# Step_motor_1.net
KiCad netlist of a schematic drawn in Altium Designer
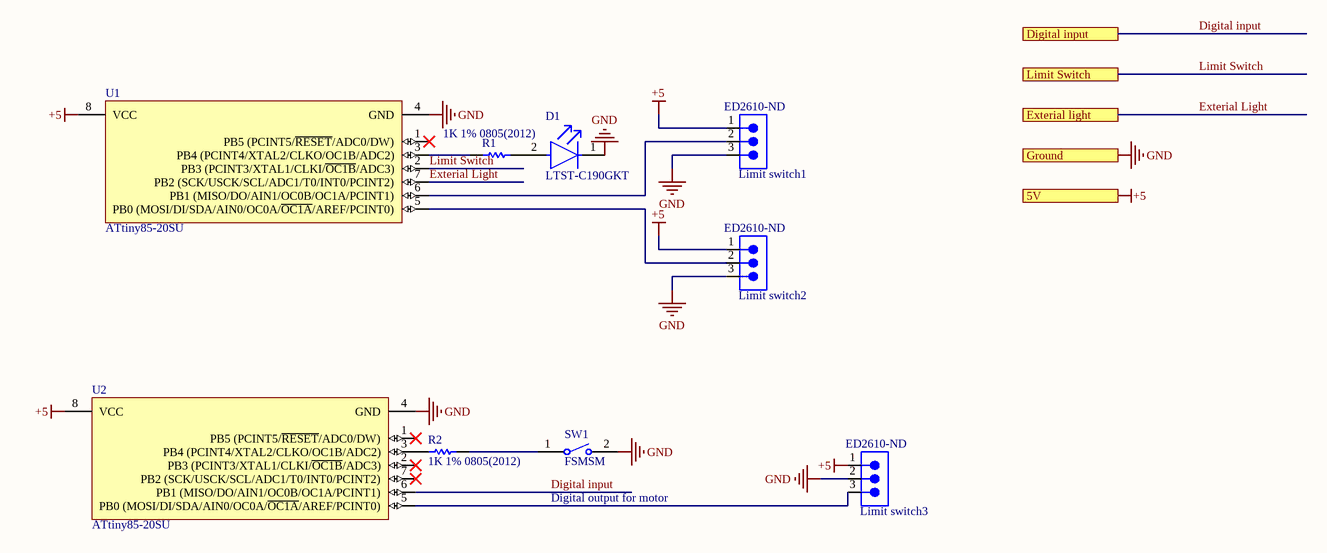
[diagram p0: Step motor 1.SchDoc]

(export (version "E")
  (design (tool "Eeschema 10.0.6"))
  (components
    (comp (ref "D1")
      (value "LTST-C190GKT")
      (footprint "FP-LTST-C190GKT-MFG")
      (description "LED GREEN CLEAR CHIP SMD")
      (fields (field (name "VOLTAGE") "2V"))
      (libsource (lib "Altium Content Vault") (part "8706943c75ba83719d021d2fdc84c58"))
    )
    (comp (ref "Limit switch1")
      (value "1x3 header 90120-0123")
      (footprint "1x3 - OSTTC032162")
      (description "HDR 1x3, 2.54mm Pitch, Vert TH")
      (fields
        (field (name "MANUFACTURER PART #") "90120-0123")
        (field (name "MANUFACTURER") "Molex")
        (field (name "SUPPLIER PART NUMBER 2") "ED2610-ND")
      )
      (libsource (lib "Connectors") (part "1x3 header 90120-0123"))
    )
    (comp (ref "Limit switch2")
      (value "1x3 header 90120-0123")
      (footprint "1x3 - OSTTC032162")
      (description "HDR 1x3, 2.54mm Pitch, Vert TH")
      (fields
        (field (name "MANUFACTURER PART #") "90120-0123")
        (field (name "MANUFACTURER") "Molex")
        (field (name "SUPPLIER PART NUMBER 2") "ED2610-ND")
      )
      (libsource (lib "Connectors") (part "1x3 header 90120-0123"))
    )
    (comp (ref "Limit switch3")
      (value "1x3 header 90120-0123")
      (footprint "1x3 - OSTTC032162")
      (description "HDR 1x3, 2.54mm Pitch, Vert TH")
      (fields
        (field (name "MANUFACTURER PART #") "90120-0123")
        (field (name "MANUFACTURER") "Molex")
        (field (name "SUPPLIER PART NUMBER 2") "ED2610-ND")
      )
      (libsource (lib "Connectors") (part "1x3 header 90120-0123"))
    )
    (comp (ref "R1")
      (value "1K 1% 0805(2012)")
      (footprint "RESC0805(2012)_M")
      (description "1K 0.125W 1% 0805 (2012 Metric)  SMD")
      (fields (field (name "TOLERANCE") "1 %") (field (name "POWER") "0.125 W"))
      (libsource (lib "Altium Content Vault") (part "RES"))
    )
    (comp (ref "R2")
      (value "1K 1% 0805(2012)")
      (footprint "RESC0805(2012)_M")
      (description "1K 0.125W 1% 0805 (2012 Metric)  SMD")
      (fields (field (name "TOLERANCE") "1 %") (field (name "POWER") "0.125 W"))
      (libsource (lib "Altium Content Vault") (part "RES"))
    )
    (comp (ref "SW1")
      (value "FSMSM")
      (footprint "TECO-FSMSM-2_V")
      (description "FSMSM Push Button Switch, 50 mA, -35 to 85 degC, 2-Pin SMD, RoHS, Bulk")
      (fields (field (name "MANUFACTURER") "TE Connectivity"))
      (libsource (lib "Altium Content Vault") (part "SW-SPST-2_C"))
    )
    (comp (ref "U1")
      (value "ATtiny85-20SU")
      (footprint "8S2_M")
      (libsource (lib "Altium Content Vault") (part "MC-8B-ATT25-IL8"))
    )
    (comp (ref "U2")
      (value "ATtiny85-20SU")
      (footprint "8S2_M")
      (libsource (lib "Altium Content Vault") (part "MC-8B-ATT25-IL8"))
    )
  )
  (nets
    (net (code "1") (name "+5") (class "Default")
      (node (ref "Limit switch1") (pin "1") (pinfunction "1_1") (pintype "passive"))
      (node (ref "Limit switch2") (pin "1") (pinfunction "1_1") (pintype "passive"))
      (node (ref "Limit switch3") (pin "1") (pinfunction "1_1") (pintype "passive"))
      (node (ref "U1") (pin "8") (pinfunction "VCC_8") (pintype "power_in"))
      (node (ref "U2") (pin "8") (pinfunction "VCC_8") (pintype "power_in"))
    )
    (net (code "2") (name "/Digital input") (class "Default")
      (node (ref "U2") (pin "6") (pinfunction "PB1_(MISO/DO/AIN1/OC0B/OC1A/PCINT1)_6") (pintype "bidirectional"))
    )
    (net (code "3") (name "/Exterial Light") (class "Default")
      (node (ref "U1") (pin "7") (pinfunction "PB2_(SCK/USCK/SCL/ADC1/T0/INT0/PCINT2)_7") (pintype "bidirectional"))
    )
    (net (code "4") (name "/Limit Switch") (class "Default")
      (node (ref "U1") (pin "2") (pinfunction "PB3_(PCINT3/XTAL1/CLKI/~{OC1B}/ADC3)_2") (pintype "bidirectional"))
    )
    (net (code "5") (name "GND") (class "Default")
      (node (ref "D1") (pin "1") (pinfunction "C_1") (pintype "passive"))
      (node (ref "Limit switch1") (pin "3") (pinfunction "3_3") (pintype "passive"))
      (node (ref "Limit switch2") (pin "3") (pinfunction "3_3") (pintype "passive"))
      (node (ref "Limit switch3") (pin "2") (pinfunction "2_2") (pintype "passive"))
      (node (ref "SW1") (pin "2") (pinfunction "2_2") (pintype "passive"))
      (node (ref "U1") (pin "4") (pinfunction "GND_4") (pintype "power_in"))
      (node (ref "U2") (pin "4") (pinfunction "GND_4") (pintype "power_in"))
    )
    (net (code "6") (name "Net-(D1-A)") (class "Default")
      (node (ref "D1") (pin "2") (pinfunction "A_2") (pintype "passive"))
      (node (ref "R1") (pin "2") (pinfunction "2_2") (pintype "passive"))
    )
    (net (code "7") (name "Net-(R2-Pad2)") (class "Default")
      (node (ref "R2") (pin "2") (pinfunction "2_2") (pintype "passive"))
      (node (ref "SW1") (pin "1") (pinfunction "1_1") (pintype "passive"))
    )
    (net (code "8") (name "Net-(U1-PB0_(MOSI{slash}DI{slash}SDA{slash}AIN0{slash}OC0A{slash}~{OC1A}{slash}AREF{slash}PCINT0))") (class "Default")
      (node (ref "Limit switch2") (pin "2") (pinfunction "2_2") (pintype "passive"))
      (node (ref "U1") (pin "5") (pinfunction "PB0_(MOSI/DI/SDA/AIN0/OC0A/~{OC1A}/AREF/PCINT0)_5") (pintype "bidirectional"))
    )
    (net (code "9") (name "Net-(U1-PB1_(MISO{slash}DO{slash}AIN1{slash}OC0B{slash}OC1A{slash}PCINT1))") (class "Default")
      (node (ref "Limit switch1") (pin "2") (pinfunction "2_2") (pintype "passive"))
      (node (ref "U1") (pin "6") (pinfunction "PB1_(MISO/DO/AIN1/OC0B/OC1A/PCINT1)_6") (pintype "bidirectional"))
    )
    (net (code "10") (name "Net-(U1-PB4_(PCINT4{slash}XTAL2{slash}CLKO{slash}OC1B{slash}ADC2))") (class "Default")
      (node (ref "R1") (pin "1") (pinfunction "1_1") (pintype "passive"))
      (node (ref "U1") (pin "3") (pinfunction "PB4_(PCINT4/XTAL2/CLKO/OC1B/ADC2)_3") (pintype "bidirectional"))
    )
    (net (code "11") (name "Net-(U2-PB0_(MOSI{slash}DI{slash}SDA{slash}AIN0{slash}OC0A{slash}~{OC1A}{slash}AREF{slash}PCINT0))") (class "Default")
      (node (ref "Limit switch3") (pin "3") (pinfunction "3_3") (pintype "passive"))
      (node (ref "U2") (pin "5") (pinfunction "PB0_(MOSI/DI/SDA/AIN0/OC0A/~{OC1A}/AREF/PCINT0)_5") (pintype "bidirectional"))
    )
    (net (code "12") (name "Net-(U2-PB4_(PCINT4{slash}XTAL2{slash}CLKO{slash}OC1B{slash}ADC2))") (class "Default")
      (node (ref "R2") (pin "1") (pinfunction "1_1") (pintype "passive"))
      (node (ref "U2") (pin "3") (pinfunction "PB4_(PCINT4/XTAL2/CLKO/OC1B/ADC2)_3") (pintype "bidirectional"))
    )
    (net (code "13") (name "unconnected-(U1-PB5_(PCINT5{slash}~{RESET}{slash}ADC0{slash}DW)-Pad1)") (class "Default")
      (node (ref "U1") (pin "1") (pinfunction "PB5_(PCINT5/~{RESET}/ADC0/DW)_1") (pintype "bidirectional+no_connect"))
    )
    (net (code "14") (name "unconnected-(U2-PB2_(SCK{slash}USCK{slash}SCL{slash}ADC1{slash}T0{slash}INT0{slash}PCINT2)-Pad7)") (class "Default")
      (node (ref "U2") (pin "7") (pinfunction "PB2_(SCK/USCK/SCL/ADC1/T0/INT0/PCINT2)_7") (pintype "bidirectional+no_connect"))
    )
    (net (code "15") (name "unconnected-(U2-PB3_(PCINT3{slash}XTAL1{slash}CLKI{slash}~{OC1B}{slash}ADC3)-Pad2)") (class "Default")
      (node (ref "U2") (pin "2") (pinfunction "PB3_(PCINT3/XTAL1/CLKI/~{OC1B}/ADC3)_2") (pintype "bidirectional+no_connect"))
    )
    (net (code "16") (name "unconnected-(U2-PB5_(PCINT5{slash}~{RESET}{slash}ADC0{slash}DW)-Pad1)") (class "Default")
      (node (ref "U2") (pin "1") (pinfunction "PB5_(PCINT5/~{RESET}/ADC0/DW)_1") (pintype "bidirectional+no_connect"))
    )
  )
)
